# CPU.net
KiCad netlist of a schematic drawn in Altium Designer
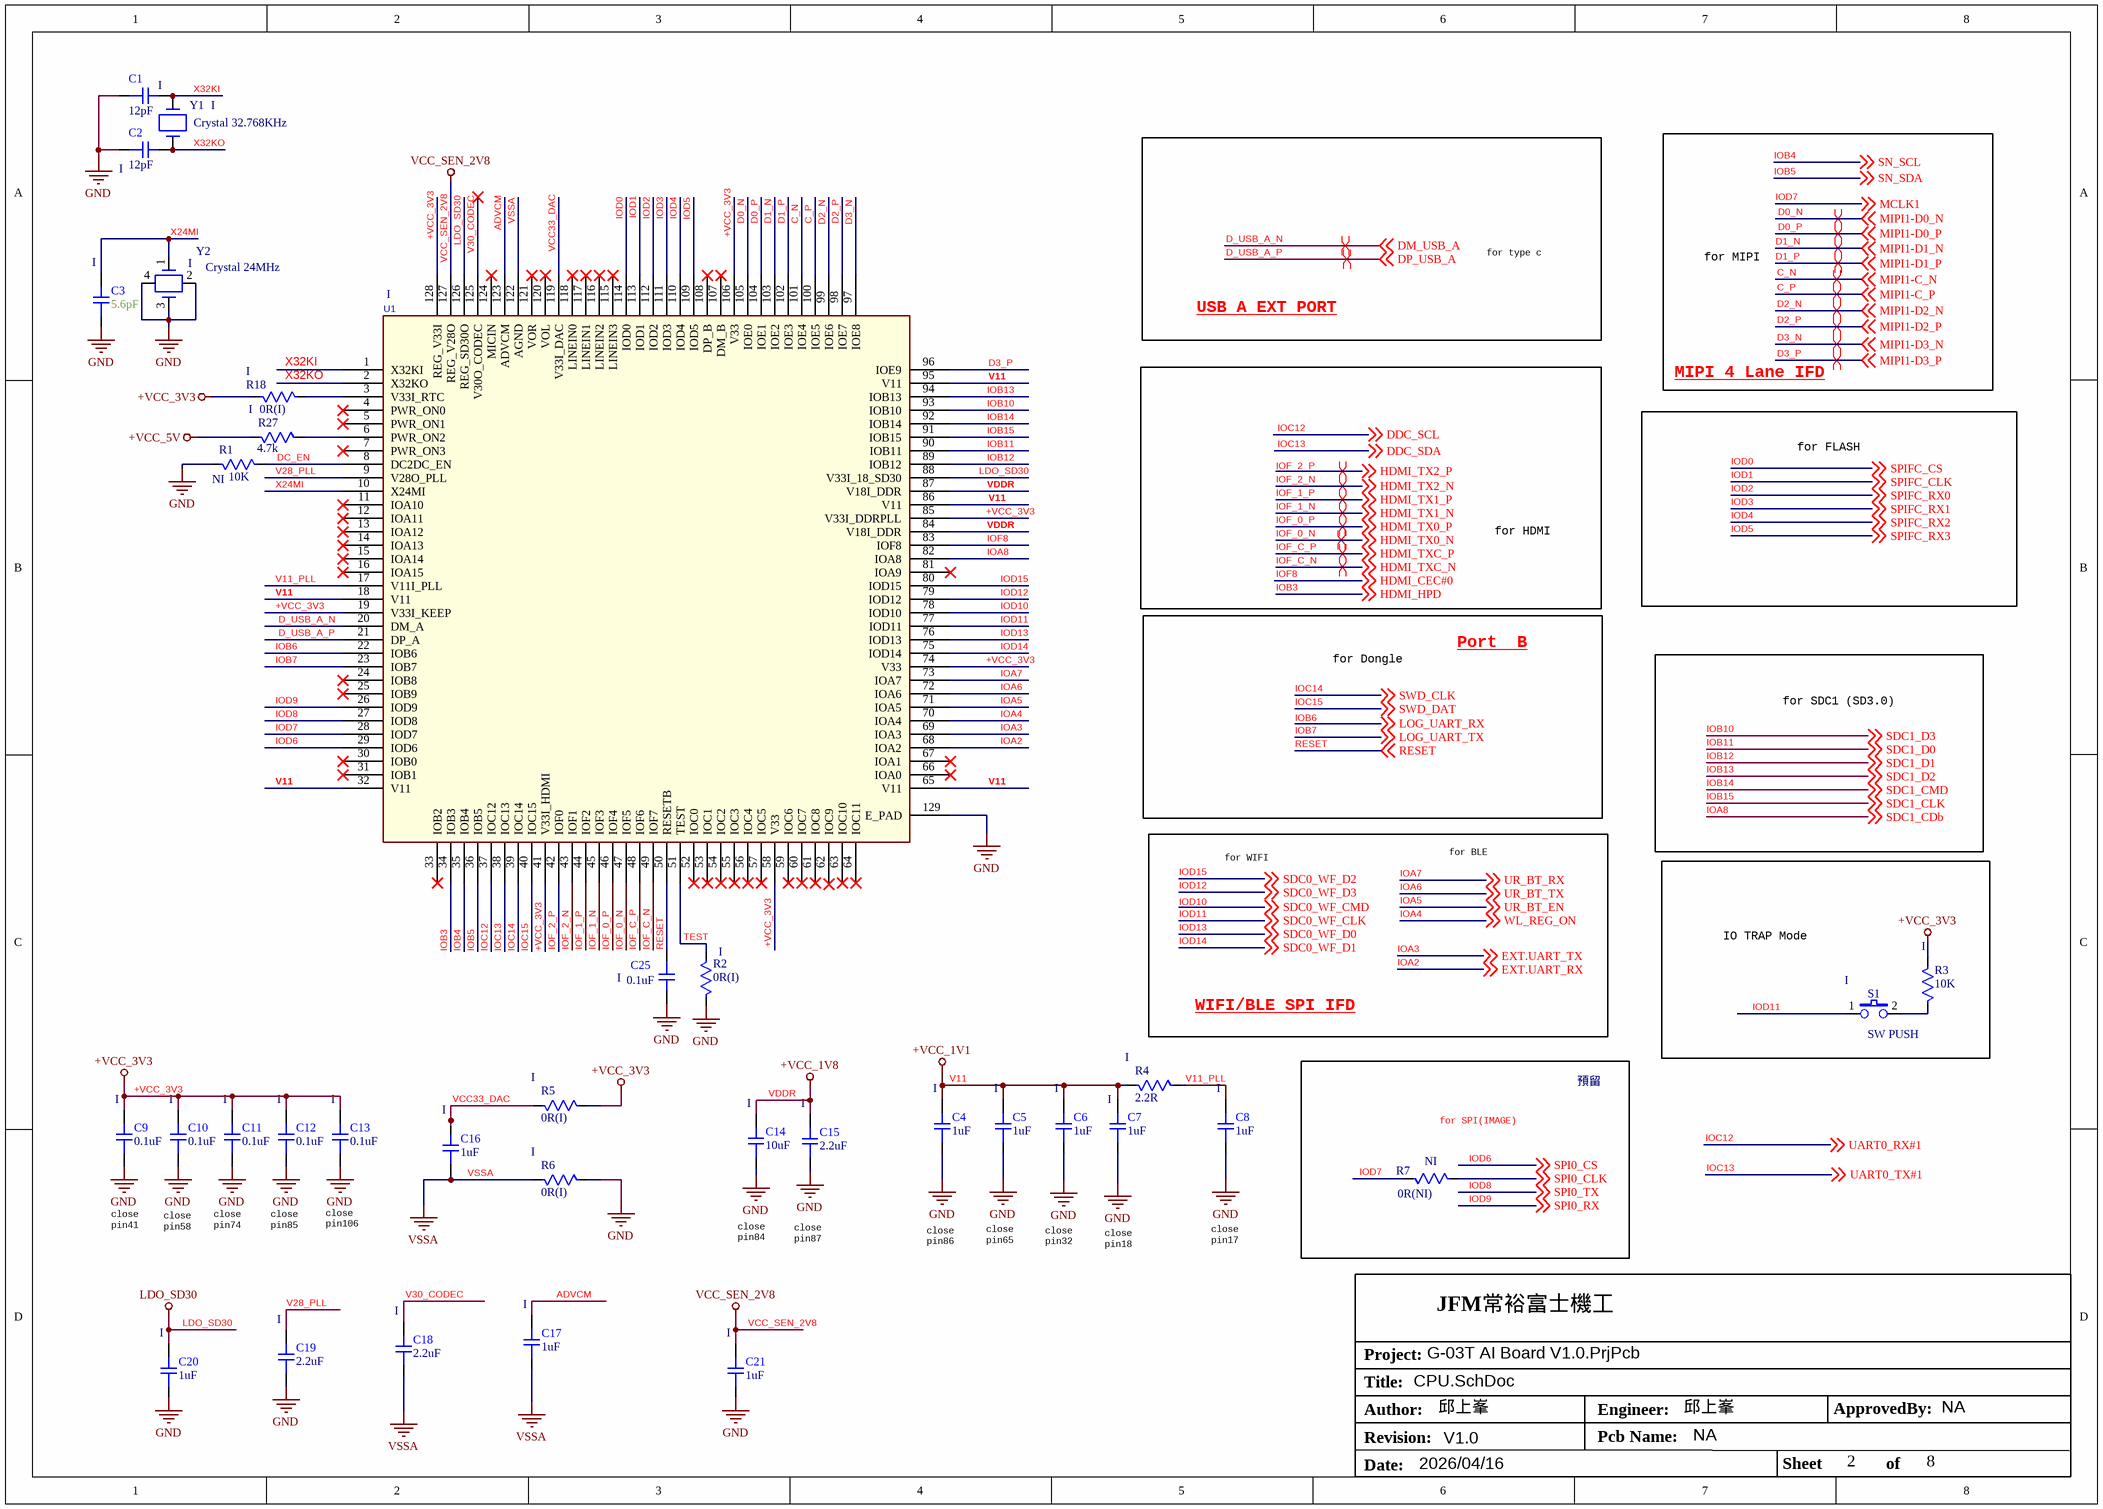
[diagram p0: CPU.SchDoc]

(export (version "E")
  (design (tool "Eeschema 10.0.6"))
  (components
    (comp (ref "C1")
      (value "12pF")
      (footprint "C0402")
      (fields (field (name "BOM") "I"))
      (libsource (lib "AMIDA7") (part "Cap"))
    )
    (comp (ref "C2")
      (value "12pF")
      (footprint "C0402")
      (fields (field (name "BOM") "I"))
      (libsource (lib "AMIDA7") (part "Cap"))
    )
    (comp (ref "C3")
      (value "5.6pF")
      (footprint "C0402")
      (fields (field (name "BOM") "I"))
      (libsource (lib "AMIDA7") (part "Cap"))
    )
    (comp (ref "C4")
      (value "1uF")
      (footprint "C0402")
      (fields (field (name "BOM") "I"))
      (libsource (lib "AMIDA7") (part "Cap"))
    )
    (comp (ref "C5")
      (value "1uF")
      (footprint "C0402")
      (fields (field (name "BOM") "I"))
      (libsource (lib "AMIDA7") (part "Cap"))
    )
    (comp (ref "C6")
      (value "1uF")
      (footprint "C0402")
      (fields (field (name "BOM") "I"))
      (libsource (lib "AMIDA7") (part "Cap"))
    )
    (comp (ref "C7")
      (value "1uF")
      (footprint "C0402")
      (fields (field (name "BOM") "I"))
      (libsource (lib "AMIDA7") (part "Cap"))
    )
    (comp (ref "C8")
      (value "1uF")
      (footprint "C0402")
      (fields (field (name "BOM") "I"))
      (libsource (lib "AMIDA7") (part "Cap"))
    )
    (comp (ref "C9")
      (value "0.1uF")
      (footprint "C0402")
      (fields (field (name "BOM") "I"))
      (libsource (lib "AMIDA7") (part "Cap"))
    )
    (comp (ref "C10")
      (value "0.1uF")
      (footprint "C0402")
      (fields (field (name "BOM") "I"))
      (libsource (lib "AMIDA7") (part "Cap"))
    )
    (comp (ref "C11")
      (value "0.1uF")
      (footprint "C0402")
      (fields (field (name "BOM") "I"))
      (libsource (lib "AMIDA7") (part "Cap"))
    )
    (comp (ref "C12")
      (value "0.1uF")
      (footprint "C0402")
      (fields (field (name "BOM") "I"))
      (libsource (lib "AMIDA7") (part "Cap"))
    )
    (comp (ref "C13")
      (value "0.1uF")
      (footprint "C0402")
      (fields (field (name "BOM") "I"))
      (libsource (lib "AMIDA7") (part "Cap"))
    )
    (comp (ref "C14")
      (value "10uF")
      (footprint "C0603")
      (fields (field (name "BOM") "I"))
      (libsource (lib "AMIDA7") (part "Cap"))
    )
    (comp (ref "C15")
      (value "2.2uF")
      (footprint "C0402")
      (fields (field (name "BOM") "I"))
      (libsource (lib "AMIDA7") (part "Cap"))
    )
    (comp (ref "C16")
      (value "1uF")
      (footprint "C0402")
      (fields (field (name "BOM") "I"))
      (libsource (lib "AMIDA7") (part "Cap"))
    )
    (comp (ref "C17")
      (value "1uF")
      (footprint "C0402")
      (fields (field (name "BOM") "I"))
      (libsource (lib "AMIDA7") (part "Cap"))
    )
    (comp (ref "C18")
      (value "2.2uF")
      (footprint "C0402")
      (fields (field (name "BOM") "I"))
      (libsource (lib "AMIDA7") (part "Cap"))
    )
    (comp (ref "C19")
      (value "2.2uF")
      (footprint "C0402")
      (fields (field (name "BOM") "I"))
      (libsource (lib "AMIDA7") (part "Cap"))
    )
    (comp (ref "C20")
      (value "1uF")
      (footprint "C0402")
      (fields (field (name "BOM") "I"))
      (libsource (lib "AMIDA7") (part "Cap"))
    )
    (comp (ref "C21")
      (value "1uF")
      (footprint "C0402")
      (fields (field (name "BOM") "I"))
      (libsource (lib "AMIDA7") (part "Cap"))
    )
    (comp (ref "C25")
      (value "0.1uF")
      (footprint "C0402")
      (fields (field (name "BOM") "I"))
      (libsource (lib "AMIDA7") (part "Cap"))
    )
    (comp (ref "R1")
      (value "10K")
      (footprint "R0603")
      (fields (field (name "BOM") "NI"))
      (libsource (lib "AMIDA7") (part "Res"))
    )
    (comp (ref "R2")
      (value "0R(I)")
      (footprint "R0402")
      (fields (field (name "BOM") "I"))
      (libsource (lib "AMIDA7") (part "Res"))
    )
    (comp (ref "R3")
      (value "10K")
      (footprint "R0402")
      (fields (field (name "BOM") "I"))
      (libsource (lib "AMIDA7") (part "Res"))
    )
    (comp (ref "R4")
      (value "2.2R")
      (footprint "R0603")
      (fields (field (name "BOM") "I"))
      (libsource (lib "AMIDA7") (part "Res"))
    )
    (comp (ref "R5")
      (value "0R(I)")
      (footprint "R0402")
      (fields (field (name "BOM") "I"))
      (libsource (lib "AMIDA7") (part "Res"))
    )
    (comp (ref "R6")
      (value "0R(I)")
      (footprint "R0402")
      (fields (field (name "BOM") "I"))
      (libsource (lib "AMIDA7") (part "Res"))
    )
    (comp (ref "R7")
      (value "0R(NI)")
      (footprint "R0402")
      (fields (field (name "BOM") "NI"))
      (libsource (lib "AMIDA7") (part "Res"))
    )
    (comp (ref "R18")
      (value "0R(I)")
      (footprint "R0402")
      (fields (field (name "BOM") "I"))
      (libsource (lib "AMIDA7") (part "Res"))
    )
    (comp (ref "R27")
      (value "4.7k")
      (footprint "R0402")
      (fields (field (name "BOM") "I"))
      (libsource (lib "AMIDA7") (part "Res"))
    )
    (comp (ref "S1")
      (value "SW PUSH")
      (footprint "Surface Mount Right Angle Switch")
      (fields (field (name "BOM") "I"))
      (libsource (lib "AMIDA7") (part "SW PUSH"))
    )
    (comp (ref "U1")
      (value "GPA7740A-LQFP128-EP")
      (footprint "TQFP128P 1600X1600X160-129N")
      (fields (field (name "BOM") "I"))
      (libsource (lib "AMIDA7") (part "GPA7740A-LQFP128-EP"))
    )
    (comp (ref "Y1")
      (value "Crystal 32.768KHz")
      (footprint "Crystal 32.768KHz")
      (description "Q-SC20S03220C5AAAF,SEIKO,l32.768KHz,12.5PF,20ppm,2.05x1.2mm")
      (fields (field (name "BOM") "I"))
      (libsource (lib "AMIDA7") (part "Crystal 32.768KHz"))
    )
    (comp (ref "Y2")
      (value "Crystal 24MHz")
      (footprint "Crystal 24MHz")
      (description "XRCGE24M000FBA1BR0,MURATA,24.0000MHZ,8PF,15PPM,2.0x1.6mm")
      (fields (field (name "BOM") "I"))
      (libsource (lib "AMIDA7") (part "Crystal 24MHz"))
    )
  )
  (nets
    (net (code "1") (name "+VCC_1V1") (class "Default")
      (node (ref "C4") (pin "2") (pinfunction "2_2") (pintype "passive"))
      (node (ref "C5") (pin "2") (pinfunction "2_2") (pintype "passive"))
      (node (ref "C6") (pin "2") (pinfunction "2_2") (pintype "passive"))
      (node (ref "C7") (pin "2") (pinfunction "2_2") (pintype "passive"))
      (node (ref "R4") (pin "1") (pinfunction "1_1") (pintype "passive"))
      (node (ref "U1") (pin "18") (pinfunction "V11_18") (pintype "passive"))
      (node (ref "U1") (pin "32") (pinfunction "V11_32") (pintype "passive"))
      (node (ref "U1") (pin "65") (pinfunction "V11_65") (pintype "passive"))
      (node (ref "U1") (pin "86") (pinfunction "V11_86") (pintype "passive"))
      (node (ref "U1") (pin "95") (pinfunction "V11_95") (pintype "passive"))
    )
    (net (code "2") (name "+VCC_1V8") (class "Default")
      (node (ref "C14") (pin "2") (pinfunction "2_2") (pintype "passive"))
      (node (ref "C15") (pin "2") (pinfunction "2_2") (pintype "passive"))
      (node (ref "U1") (pin "84") (pinfunction "V18I_DDR_84") (pintype "passive"))
      (node (ref "U1") (pin "87") (pinfunction "V18I_DDR_87") (pintype "passive"))
    )
    (net (code "3") (name "+VCC_3V3") (class "Default")
      (node (ref "C10") (pin "2") (pinfunction "2_2") (pintype "passive"))
      (node (ref "C11") (pin "2") (pinfunction "2_2") (pintype "passive"))
      (node (ref "C12") (pin "2") (pinfunction "2_2") (pintype "passive"))
      (node (ref "C13") (pin "2") (pinfunction "2_2") (pintype "passive"))
      (node (ref "C9") (pin "2") (pinfunction "2_2") (pintype "passive"))
      (node (ref "R18") (pin "2") (pinfunction "2_2") (pintype "passive"))
      (node (ref "R3") (pin "1") (pinfunction "1_1") (pintype "passive"))
      (node (ref "R5") (pin "2") (pinfunction "2_2") (pintype "passive"))
      (node (ref "U1") (pin "106") (pinfunction "V33_106") (pintype "passive"))
      (node (ref "U1") (pin "128") (pinfunction "REG_V33I_128") (pintype "passive"))
      (node (ref "U1") (pin "19") (pinfunction "V33I_KEEP_19") (pintype "passive"))
      (node (ref "U1") (pin "41") (pinfunction "V33I_HDMI_41") (pintype "passive"))
      (node (ref "U1") (pin "58") (pinfunction "V33_58") (pintype "passive"))
      (node (ref "U1") (pin "74") (pinfunction "V33_74") (pintype "passive"))
      (node (ref "U1") (pin "85") (pinfunction "V33I_DDRPLL_85") (pintype "passive"))
    )
    (net (code "4") (name "+VCC_5V") (class "Default")
      (node (ref "R27") (pin "2") (pinfunction "2_2") (pintype "passive"))
    )
    (net (code "5") (name "/ADVCM") (class "Default")
      (node (ref "C17") (pin "2") (pinfunction "2_2") (pintype "passive"))
      (node (ref "U1") (pin "123") (pinfunction "ADVCM_123") (pintype "passive"))
    )
    (net (code "6") (name "/DC_EN") (class "Default")
      (node (ref "R1") (pin "1") (pinfunction "1_1") (pintype "passive"))
      (node (ref "U1") (pin "8") (pinfunction "DC2DC_EN_8") (pintype "passive"))
    )
    (net (code "7") (name "/IOB6") (class "Default")
      (node (ref "U1") (pin "22") (pinfunction "IOB6_22") (pintype "passive"))
    )
    (net (code "8") (name "/IOD10") (class "Default")
      (node (ref "U1") (pin "78") (pinfunction "IOD10_78") (pintype "passive"))
    )
    (net (code "9") (name "/IOF_2_P") (class "Default")
      (node (ref "U1") (pin "42") (pinfunction "IOF0_42") (pintype "passive"))
    )
    (net (code "10") (name "/TEST") (class "Default")
      (node (ref "R2") (pin "2") (pinfunction "2_2") (pintype "passive"))
      (node (ref "U1") (pin "51") (pinfunction "TEST_51") (pintype "passive"))
    )
    (net (code "11") (name "/V11_PLL") (class "Default")
      (node (ref "C8") (pin "2") (pinfunction "2_2") (pintype "passive"))
      (node (ref "R4") (pin "2") (pinfunction "2_2") (pintype "passive"))
      (node (ref "U1") (pin "17") (pinfunction "V11I_PLL_17") (pintype "passive"))
    )
    (net (code "12") (name "/V28_PLL") (class "Default")
      (node (ref "C19") (pin "2") (pinfunction "2_2") (pintype "passive"))
      (node (ref "U1") (pin "9") (pinfunction "V28O_PLL_9") (pintype "passive"))
    )
    (net (code "13") (name "/V30_CODEC") (class "Default")
      (node (ref "C18") (pin "2") (pinfunction "2_2") (pintype "passive"))
      (node (ref "U1") (pin "125") (pinfunction "V30O_CODEC_125") (pintype "passive"))
    )
    (net (code "14") (name "/VCC33_DAC") (class "Default")
      (node (ref "C16") (pin "2") (pinfunction "2_2") (pintype "passive"))
      (node (ref "R5") (pin "1") (pinfunction "1_1") (pintype "passive"))
      (node (ref "U1") (pin "119") (pinfunction "V33I_DAC_119") (pintype "passive"))
    )
    (net (code "15") (name "/X24MI") (class "Default")
      (node (ref "C3") (pin "2") (pinfunction "2_2") (pintype "passive"))
      (node (ref "U1") (pin "10") (pinfunction "X24MI_10") (pintype "passive"))
      (node (ref "Y2") (pin "1") (pinfunction "1_1") (pintype "passive"))
    )
    (net (code "16") (name "/X32KI") (class "Default")
      (node (ref "C1") (pin "2") (pinfunction "2_2") (pintype "passive"))
      (node (ref "U1") (pin "1") (pinfunction "X32KI_1") (pintype "passive"))
      (node (ref "Y1") (pin "2") (pinfunction "2_2") (pintype "passive"))
    )
    (net (code "17") (name "/X32KO") (class "Default")
      (node (ref "C2") (pin "2") (pinfunction "2_2") (pintype "passive"))
      (node (ref "U1") (pin "2") (pinfunction "X32KO_2") (pintype "passive"))
      (node (ref "Y1") (pin "1") (pinfunction "1_1") (pintype "passive"))
    )
    (net (code "18") (name "DDC_SCL") (class "Default")
      (node (ref "U1") (pin "37") (pinfunction "IOC12_37") (pintype "passive"))
    )
    (net (code "19") (name "DDC_SDA") (class "Default")
      (node (ref "U1") (pin "38") (pinfunction "IOC13_38") (pintype "passive"))
    )
    (net (code "20") (name "DM_USB_A") (class "Default")
      (node (ref "U1") (pin "20") (pinfunction "DM_A_20") (pintype "passive"))
    )
    (net (code "21") (name "DP_USB_A") (class "Default")
      (node (ref "U1") (pin "21") (pinfunction "DP_A_21") (pintype "passive"))
    )
    (net (code "22") (name "EXT.UART_RX") (class "Default")
      (node (ref "U1") (pin "68") (pinfunction "IOA2_68") (pintype "passive"))
    )
    (net (code "23") (name "EXT.UART_TX") (class "Default")
      (node (ref "U1") (pin "69") (pinfunction "IOA3_69") (pintype "passive"))
    )
    (net (code "24") (name "GND") (class "Default")
      (node (ref "C1") (pin "1") (pinfunction "1_1") (pintype "passive"))
      (node (ref "C10") (pin "1") (pinfunction "1_1") (pintype "passive"))
      (node (ref "C11") (pin "1") (pinfunction "1_1") (pintype "passive"))
      (node (ref "C12") (pin "1") (pinfunction "1_1") (pintype "passive"))
      (node (ref "C13") (pin "1") (pinfunction "1_1") (pintype "passive"))
      (node (ref "C14") (pin "1") (pinfunction "1_1") (pintype "passive"))
      (node (ref "C15") (pin "1") (pinfunction "1_1") (pintype "passive"))
      (node (ref "C19") (pin "1") (pinfunction "1_1") (pintype "passive"))
      (node (ref "C2") (pin "1") (pinfunction "1_1") (pintype "passive"))
      (node (ref "C20") (pin "1") (pinfunction "1_1") (pintype "passive"))
      (node (ref "C21") (pin "1") (pinfunction "1_1") (pintype "passive"))
      (node (ref "C25") (pin "2") (pinfunction "2_2") (pintype "passive"))
      (node (ref "C3") (pin "1") (pinfunction "1_1") (pintype "passive"))
      (node (ref "C4") (pin "1") (pinfunction "1_1") (pintype "passive"))
      (node (ref "C5") (pin "1") (pinfunction "1_1") (pintype "passive"))
      (node (ref "C6") (pin "1") (pinfunction "1_1") (pintype "passive"))
      (node (ref "C7") (pin "1") (pinfunction "1_1") (pintype "passive"))
      (node (ref "C8") (pin "1") (pinfunction "1_1") (pintype "passive"))
      (node (ref "C9") (pin "1") (pinfunction "1_1") (pintype "passive"))
      (node (ref "R1") (pin "2") (pinfunction "2_2") (pintype "passive"))
      (node (ref "R2") (pin "1") (pinfunction "1_1") (pintype "passive"))
      (node (ref "R6") (pin "2") (pinfunction "2_2") (pintype "passive"))
      (node (ref "U1") (pin "129") (pinfunction "E_PAD_129") (pintype "passive"))
      (node (ref "Y2") (pin "2") (pinfunction "2_2") (pintype "passive"))
      (node (ref "Y2") (pin "3") (pinfunction "3_3") (pintype "passive"))
      (node (ref "Y2") (pin "4") (pinfunction "4_4") (pintype "passive"))
    )
    (net (code "25") (name "HDMI_CEC#0") (class "Default")
      (node (ref "U1") (pin "83") (pinfunction "IOF8_83") (pintype "passive"))
    )
    (net (code "26") (name "HDMI_HPD") (class "Default")
      (node (ref "U1") (pin "34") (pinfunction "IOB3_34") (pintype "passive"))
    )
    (net (code "27") (name "HDMI_TX0_N") (class "Default")
      (node (ref "U1") (pin "47") (pinfunction "IOF5_47") (pintype "passive"))
    )
    (net (code "28") (name "HDMI_TX0_P") (class "Default")
      (node (ref "U1") (pin "46") (pinfunction "IOF4_46") (pintype "passive"))
    )
    (net (code "29") (name "HDMI_TX1_N") (class "Default")
      (node (ref "U1") (pin "45") (pinfunction "IOF3_45") (pintype "passive"))
    )
    (net (code "30") (name "HDMI_TX1_P") (class "Default")
      (node (ref "U1") (pin "44") (pinfunction "IOF2_44") (pintype "passive"))
    )
    (net (code "31") (name "HDMI_TX2_N") (class "Default")
      (node (ref "U1") (pin "43") (pinfunction "IOF1_43") (pintype "passive"))
    )
    (net (code "33") (name "HDMI_TXC_N") (class "Default")
      (node (ref "U1") (pin "49") (pinfunction "IOF7_49") (pintype "passive"))
    )
    (net (code "34") (name "HDMI_TXC_P") (class "Default")
      (node (ref "U1") (pin "48") (pinfunction "IOF6_48") (pintype "passive"))
    )
    (net (code "35") (name "LDO_SD30") (class "Default")
      (node (ref "C20") (pin "2") (pinfunction "2_2") (pintype "passive"))
      (node (ref "U1") (pin "126") (pinfunction "REG_SD30O_126") (pintype "passive"))
      (node (ref "U1") (pin "88") (pinfunction "V33I_18_SD30_88") (pintype "passive"))
    )
    (net (code "37") (name "LOG_UART_TX") (class "Default")
      (node (ref "U1") (pin "23") (pinfunction "IOB7_23") (pintype "passive"))
    )
    (net (code "38") (name "MCLK1") (class "Default")
      (node (ref "R7") (pin "1") (pinfunction "1_1") (pintype "passive"))
      (node (ref "U1") (pin "28") (pinfunction "IOD7_28") (pintype "passive"))
    )
    (net (code "39") (name "MIPI1-C_N") (class "Default")
      (node (ref "U1") (pin "101") (pinfunction "IOE4_101") (pintype "passive"))
    )
    (net (code "40") (name "MIPI1-C_P") (class "Default")
      (node (ref "U1") (pin "100") (pinfunction "IOE5_100") (pintype "passive"))
    )
    (net (code "41") (name "MIPI1-D0_N") (class "Default")
      (node (ref "U1") (pin "105") (pinfunction "IOE0_105") (pintype "passive"))
    )
    (net (code "42") (name "MIPI1-D0_P") (class "Default")
      (node (ref "U1") (pin "104") (pinfunction "IOE1_104") (pintype "passive"))
    )
    (net (code "43") (name "MIPI1-D1_N") (class "Default")
      (node (ref "U1") (pin "103") (pinfunction "IOE2_103") (pintype "passive"))
    )
    (net (code "44") (name "MIPI1-D1_P") (class "Default")
      (node (ref "U1") (pin "102") (pinfunction "IOE3_102") (pintype "passive"))
    )
    (net (code "45") (name "MIPI1-D2_N") (class "Default")
      (node (ref "U1") (pin "99") (pinfunction "IOE6_99") (pintype "passive"))
    )
    (net (code "46") (name "MIPI1-D2_P") (class "Default")
      (node (ref "U1") (pin "98") (pinfunction "IOE7_98") (pintype "passive"))
    )
    (net (code "47") (name "MIPI1-D3_N") (class "Default")
      (node (ref "U1") (pin "97") (pinfunction "IOE8_97") (pintype "passive"))
    )
    (net (code "48") (name "MIPI1-D3_P") (class "Default")
      (node (ref "U1") (pin "96") (pinfunction "IOE9_96") (pintype "passive"))
    )
    (net (code "49") (name "Net-(R3-Pad2)") (class "Default")
      (node (ref "R3") (pin "2") (pinfunction "2_2") (pintype "passive"))
      (node (ref "S1") (pin "2") (pinfunction "2_2") (pintype "passive"))
    )
    (net (code "50") (name "Net-(U1-PWR_ON2)") (class "Default")
      (node (ref "R27") (pin "1") (pinfunction "1_1") (pintype "passive"))
      (node (ref "U1") (pin "6") (pinfunction "PWR_ON2_6") (pintype "passive"))
    )
    (net (code "51") (name "Net-(U1-V33I_RTC)") (class "Default")
      (node (ref "R18") (pin "1") (pinfunction "1_1") (pintype "passive"))
      (node (ref "U1") (pin "3") (pinfunction "V33I_RTC_3") (pintype "passive"))
    )
    (net (code "52") (name "RESET") (class "Default")
      (node (ref "C25") (pin "1") (pinfunction "1_1") (pintype "passive"))
      (node (ref "U1") (pin "50") (pinfunction "RESETB_50") (pintype "passive"))
    )
    (net (code "53") (name "SDC0_WF_CLK") (class "Default")
      (node (ref "S1") (pin "1") (pinfunction "1_1") (pintype "passive"))
      (node (ref "U1") (pin "77") (pinfunction "IOD11_77") (pintype "passive"))
    )
    (net (code "55") (name "SDC0_WF_D0") (class "Default")
      (node (ref "U1") (pin "76") (pinfunction "IOD13_76") (pintype "passive"))
    )
    (net (code "56") (name "SDC0_WF_D1") (class "Default")
      (node (ref "U1") (pin "75") (pinfunction "IOD14_75") (pintype "passive"))
    )
    (net (code "57") (name "SDC0_WF_D2") (class "Default")
      (node (ref "U1") (pin "80") (pinfunction "IOD15_80") (pintype "passive"))
    )
    (net (code "58") (name "SDC0_WF_D3") (class "Default")
      (node (ref "U1") (pin "79") (pinfunction "IOD12_79") (pintype "passive"))
    )
    (net (code "59") (name "SDC1_CDb") (class "Default")
      (node (ref "U1") (pin "82") (pinfunction "IOA8_82") (pintype "passive"))
    )
    (net (code "60") (name "SDC1_CLK") (class "Default")
      (node (ref "U1") (pin "91") (pinfunction "IOB15_91") (pintype "passive"))
    )
    (net (code "61") (name "SDC1_CMD") (class "Default")
      (node (ref "U1") (pin "92") (pinfunction "IOB14_92") (pintype "passive"))
    )
    (net (code "62") (name "SDC1_D0") (class "Default")
      (node (ref "U1") (pin "90") (pinfunction "IOB11_90") (pintype "passive"))
    )
    (net (code "63") (name "SDC1_D1") (class "Default")
      (node (ref "U1") (pin "89") (pinfunction "IOB12_89") (pintype "passive"))
    )
    (net (code "64") (name "SDC1_D2") (class "Default")
      (node (ref "U1") (pin "94") (pinfunction "IOB13_94") (pintype "passive"))
    )
    (net (code "65") (name "SDC1_D3") (class "Default")
      (node (ref "U1") (pin "93") (pinfunction "IOB10_93") (pintype "passive"))
    )
    (net (code "66") (name "SN_SCL") (class "Default")
      (node (ref "U1") (pin "35") (pinfunction "IOB4_35") (pintype "passive"))
    )
    (net (code "67") (name "SN_SDA") (class "Default")
      (node (ref "U1") (pin "36") (pinfunction "IOB5_36") (pintype "passive"))
    )
    (net (code "68") (name "SPI0_CLK") (class "Default")
      (node (ref "R7") (pin "2") (pinfunction "2_2") (pintype "passive"))
    )
    (net (code "69") (name "SPI0_CS") (class "Default")
      (node (ref "U1") (pin "29") (pinfunction "IOD6_29") (pintype "passive"))
    )
    (net (code "70") (name "SPI0_RX") (class "Default")
      (node (ref "U1") (pin "26") (pinfunction "IOD9_26") (pintype "passive"))
    )
    (net (code "71") (name "SPI0_TX") (class "Default")
      (node (ref "U1") (pin "27") (pinfunction "IOD8_27") (pintype "passive"))
    )
    (net (code "72") (name "SPIFC_CLK") (class "Default")
      (node (ref "U1") (pin "113") (pinfunction "IOD1_113") (pintype "passive"))
    )
    (net (code "73") (name "SPIFC_CS") (class "Default")
      (node (ref "U1") (pin "114") (pinfunction "IOD0_114") (pintype "passive"))
    )
    (net (code "74") (name "SPIFC_RX0") (class "Default")
      (node (ref "U1") (pin "112") (pinfunction "IOD2_112") (pintype "passive"))
    )
    (net (code "75") (name "SPIFC_RX1") (class "Default")
      (node (ref "U1") (pin "111") (pinfunction "IOD3_111") (pintype "passive"))
    )
    (net (code "76") (name "SPIFC_RX2") (class "Default")
      (node (ref "U1") (pin "110") (pinfunction "IOD4_110") (pintype "passive"))
    )
    (net (code "77") (name "SPIFC_RX3") (class "Default")
      (node (ref "U1") (pin "109") (pinfunction "IOD5_109") (pintype "passive"))
    )
    (net (code "78") (name "SWD_CLK") (class "Default")
      (node (ref "U1") (pin "39") (pinfunction "IOC14_39") (pintype "passive"))
    )
    (net (code "79") (name "SWD_DAT") (class "Default")
      (node (ref "U1") (pin "40") (pinfunction "IOC15_40") (pintype "passive"))
    )
    (net (code "80") (name "UR_BT_EN") (class "Default")
      (node (ref "U1") (pin "71") (pinfunction "IOA5_71") (pintype "passive"))
    )
    (net (code "81") (name "UR_BT_RX") (class "Default")
      (node (ref "U1") (pin "73") (pinfunction "IOA7_73") (pintype "passive"))
    )
    (net (code "82") (name "UR_BT_TX") (class "Default")
      (node (ref "U1") (pin "72") (pinfunction "IOA6_72") (pintype "passive"))
    )
    (net (code "83") (name "VCC_SEN_2V8") (class "Default")
      (node (ref "C21") (pin "2") (pinfunction "2_2") (pintype "passive"))
      (node (ref "U1") (pin "127") (pinfunction "REG_V28O_127") (pintype "passive"))
    )
    (net (code "84") (name "VSSA") (class "Default")
      (node (ref "C16") (pin "1") (pinfunction "1_1") (pintype "passive"))
      (node (ref "C17") (pin "1") (pinfunction "1_1") (pintype "passive"))
      (node (ref "C18") (pin "1") (pinfunction "1_1") (pintype "passive"))
      (node (ref "R6") (pin "1") (pinfunction "1_1") (pintype "passive"))
      (node (ref "U1") (pin "122") (pinfunction "AGND_122") (pintype "passive"))
    )
    (net (code "85") (name "WL_REG_ON") (class "Default")
      (node (ref "U1") (pin "70") (pinfunction "IOA4_70") (pintype "passive"))
    )
    (net (code "86") (name "unconnected-(U1-DM_B-Pad107)") (class "Default")
      (node (ref "U1") (pin "107") (pinfunction "DM_B_107") (pintype "passive+no_connect"))
    )
    (net (code "87") (name "unconnected-(U1-DP_B-Pad108)") (class "Default")
      (node (ref "U1") (pin "108") (pinfunction "DP_B_108") (pintype "passive+no_connect"))
    )
    (net (code "88") (name "unconnected-(U1-IOA0-Pad66)") (class "Default")
      (node (ref "U1") (pin "66") (pinfunction "IOA0_66") (pintype "passive+no_connect"))
    )
    (net (code "89") (name "unconnected-(U1-IOA1-Pad67)") (class "Default")
      (node (ref "U1") (pin "67") (pinfunction "IOA1_67") (pintype "passive+no_connect"))
    )
    (net (code "90") (name "unconnected-(U1-IOA9-Pad81)") (class "Default")
      (node (ref "U1") (pin "81") (pinfunction "IOA9_81") (pintype "passive+no_connect"))
    )
    (net (code "91") (name "unconnected-(U1-IOA10-Pad11)") (class "Default")
      (node (ref "U1") (pin "11") (pinfunction "IOA10_11") (pintype "passive+no_connect"))
    )
    (net (code "92") (name "unconnected-(U1-IOA11-Pad12)") (class "Default")
      (node (ref "U1") (pin "12") (pinfunction "IOA11_12") (pintype "passive+no_connect"))
    )
    (net (code "93") (name "unconnected-(U1-IOA12-Pad13)") (class "Default")
      (node (ref "U1") (pin "13") (pinfunction "IOA12_13") (pintype "passive+no_connect"))
    )
    (net (code "94") (name "unconnected-(U1-IOA13-Pad14)") (class "Default")
      (node (ref "U1") (pin "14") (pinfunction "IOA13_14") (pintype "passive+no_connect"))
    )
    (net (code "95") (name "unconnected-(U1-IOA14-Pad15)") (class "Default")
      (node (ref "U1") (pin "15") (pinfunction "IOA14_15") (pintype "passive+no_connect"))
    )
    (net (code "96") (name "unconnected-(U1-IOA15-Pad16)") (class "Default")
      (node (ref "U1") (pin "16") (pinfunction "IOA15_16") (pintype "passive+no_connect"))
    )
    (net (code "97") (name "unconnected-(U1-IOB0-Pad30)") (class "Default")
      (node (ref "U1") (pin "30") (pinfunction "IOB0_30") (pintype "passive+no_connect"))
    )
    (net (code "98") (name "unconnected-(U1-IOB1-Pad31)") (class "Default")
      (node (ref "U1") (pin "31") (pinfunction "IOB1_31") (pintype "passive+no_connect"))
    )
    (net (code "99") (name "unconnected-(U1-IOB2-Pad33)") (class "Default")
      (node (ref "U1") (pin "33") (pinfunction "IOB2_33") (pintype "passive+no_connect"))
    )
    (net (code "100") (name "unconnected-(U1-IOB8-Pad24)") (class "Default")
      (node (ref "U1") (pin "24") (pinfunction "IOB8_24") (pintype "passive+no_connect"))
    )
    (net (code "101") (name "unconnected-(U1-IOB9-Pad25)") (class "Default")
      (node (ref "U1") (pin "25") (pinfunction "IOB9_25") (pintype "passive+no_connect"))
    )
    (net (code "102") (name "unconnected-(U1-IOC0-Pad52)") (class "Default")
      (node (ref "U1") (pin "52") (pinfunction "IOC0_52") (pintype "passive+no_connect"))
    )
    (net (code "103") (name "unconnected-(U1-IOC1-Pad53)") (class "Default")
      (node (ref "U1") (pin "53") (pinfunction "IOC1_53") (pintype "passive+no_connect"))
    )
    (net (code "104") (name "unconnected-(U1-IOC2-Pad54)") (class "Default")
      (node (ref "U1") (pin "54") (pinfunction "IOC2_54") (pintype "passive+no_connect"))
    )
    (net (code "105") (name "unconnected-(U1-IOC3-Pad55)") (class "Default")
      (node (ref "U1") (pin "55") (pinfunction "IOC3_55") (pintype "passive+no_connect"))
    )
    (net (code "106") (name "unconnected-(U1-IOC4-Pad56)") (class "Default")
      (node (ref "U1") (pin "56") (pinfunction "IOC4_56") (pintype "passive+no_connect"))
    )
    (net (code "107") (name "unconnected-(U1-IOC5-Pad57)") (class "Default")
      (node (ref "U1") (pin "57") (pinfunction "IOC5_57") (pintype "passive+no_connect"))
    )
    (net (code "108") (name "unconnected-(U1-IOC6-Pad59)") (class "Default")
      (node (ref "U1") (pin "59") (pinfunction "IOC6_59") (pintype "passive+no_connect"))
    )
    (net (code "109") (name "unconnected-(U1-IOC7-Pad60)") (class "Default")
      (node (ref "U1") (pin "60") (pinfunction "IOC7_60") (pintype "passive+no_connect"))
    )
    (net (code "110") (name "unconnected-(U1-IOC8-Pad61)") (class "Default")
      (node (ref "U1") (pin "61") (pinfunction "IOC8_61") (pintype "passive+no_connect"))
    )
    (net (code "111") (name "unconnected-(U1-IOC9-Pad62)") (class "Default")
      (node (ref "U1") (pin "62") (pinfunction "IOC9_62") (pintype "passive"))
    )
    (net (code "112") (name "unconnected-(U1-IOC10-Pad63)") (class "Default")
      (node (ref "U1") (pin "63") (pinfunction "IOC10_63") (pintype "passive+no_connect"))
    )
    (net (code "113") (name "unconnected-(U1-IOC11-Pad64)") (class "Default")
      (node (ref "U1") (pin "64") (pinfunction "IOC11_64") (pintype "passive+no_connect"))
    )
    (net (code "114") (name "unconnected-(U1-LINEIN0-Pad118)") (class "Default")
      (node (ref "U1") (pin "118") (pinfunction "LINEIN0_118") (pintype "passive+no_connect"))
    )
    (net (code "115") (name "unconnected-(U1-LINEIN1-Pad117)") (class "Default")
      (node (ref "U1") (pin "117") (pinfunction "LINEIN1_117") (pintype "passive+no_connect"))
    )
    (net (code "116") (name "unconnected-(U1-LINEIN2-Pad116)") (class "Default")
      (node (ref "U1") (pin "116") (pinfunction "LINEIN2_116") (pintype "passive+no_connect"))
    )
    (net (code "117") (name "unconnected-(U1-LINEIN3-Pad115)") (class "Default")
      (node (ref "U1") (pin "115") (pinfunction "LINEIN3_115") (pintype "passive+no_connect"))
    )
    (net (code "118") (name "unconnected-(U1-MICIN-Pad124)") (class "Default")
      (node (ref "U1") (pin "124") (pinfunction "MICIN_124") (pintype "passive+no_connect"))
    )
    (net (code "119") (name "unconnected-(U1-PWR_ON0-Pad4)") (class "Default")
      (node (ref "U1") (pin "4") (pinfunction "PWR_ON0_4") (pintype "passive+no_connect"))
    )
    (net (code "120") (name "unconnected-(U1-PWR_ON1-Pad5)") (class "Default")
      (node (ref "U1") (pin "5") (pinfunction "PWR_ON1_5") (pintype "passive+no_connect"))
    )
    (net (code "121") (name "unconnected-(U1-PWR_ON3-Pad7)") (class "Default")
      (node (ref "U1") (pin "7") (pinfunction "PWR_ON3_7") (pintype "passive+no_connect"))
    )
    (net (code "122") (name "unconnected-(U1-VOL-Pad120)") (class "Default")
      (node (ref "U1") (pin "120") (pinfunction "VOL_120") (pintype "passive+no_connect"))
    )
    (net (code "123") (name "unconnected-(U1-VOR-Pad121)") (class "Default")
      (node (ref "U1") (pin "121") (pinfunction "VOR_121") (pintype "passive+no_connect"))
    )
  )
)
